# Microcontroller.net
KiCad netlist of a schematic drawn in Altium Designer
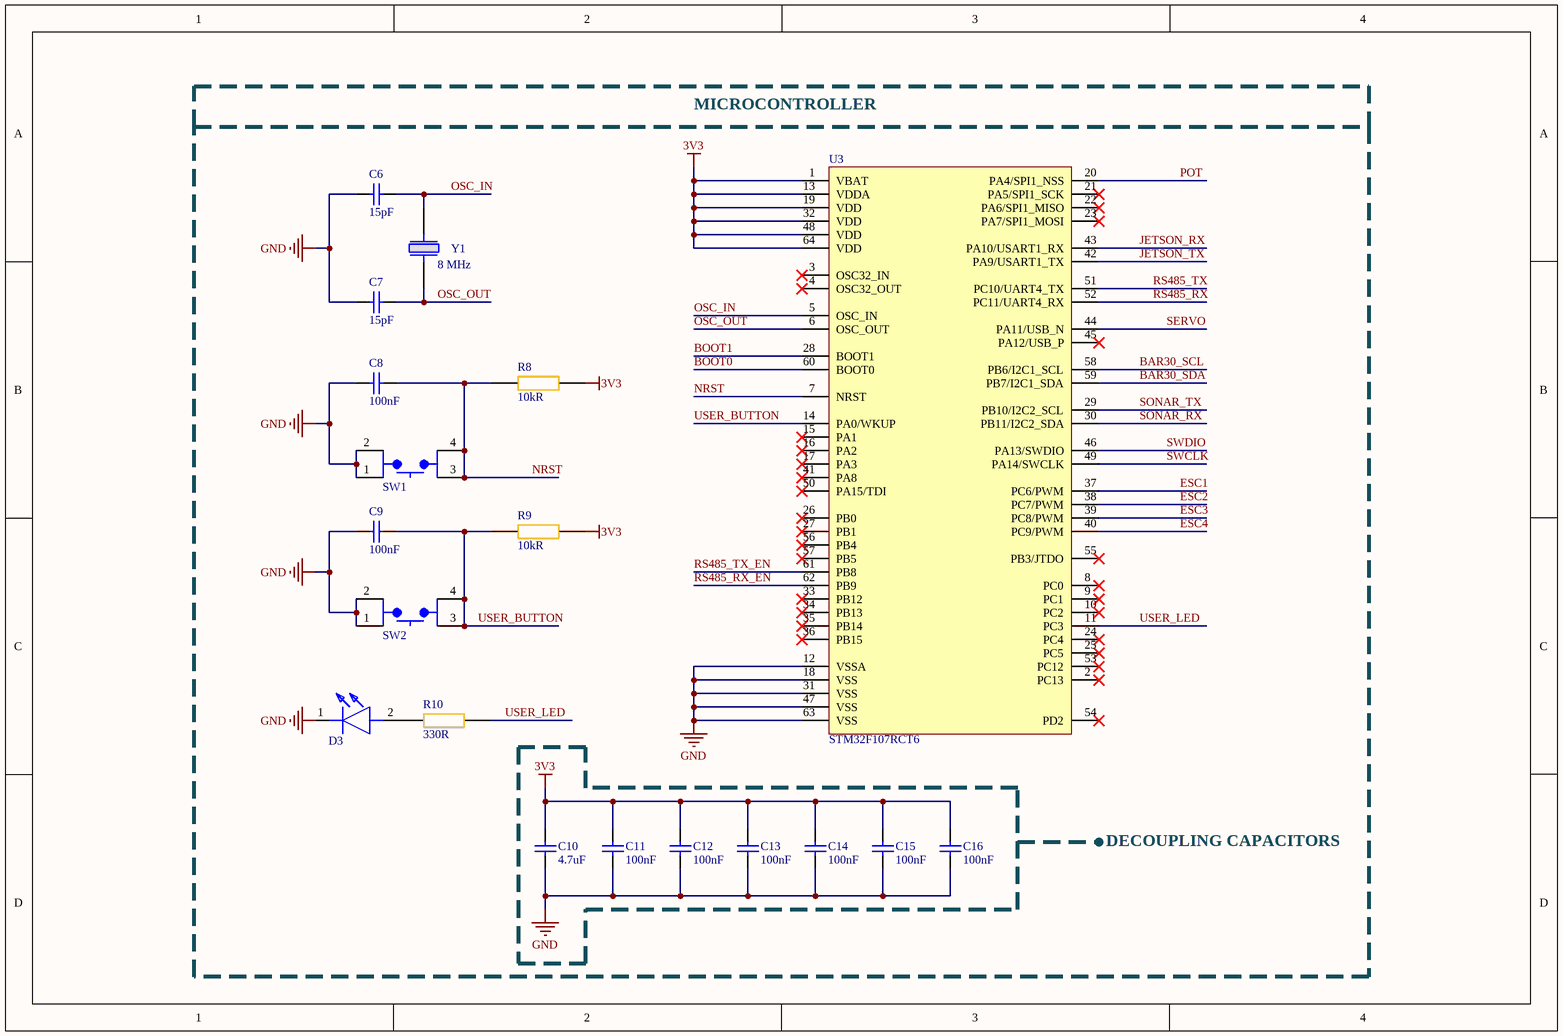
[diagram p0: Microcontroller.SchDoc]

(export (version "E")
  (design (tool "Eeschema 10.0.6"))
  (components
    (comp (ref "C6")
      (value "15pF")
      (footprint "WCAP-CSGP_0603_L1.6W0.8H0.8_Reflow")
      (description "WCAP-CSGP Multilayer Ceramic Chip Capacitor, General Purpose, size 0603, NP0, 15pF, 16VDC")
      (fields
        (field (name "MANUFACTURER PART NUMBER") "885012006018")
        (field (name "MANUFACTURER") "Wurth Elektronik")
      )
      (libsource (lib "WE - Passive Components") (part "Capacitor_Non-Polarized"))
    )
    (comp (ref "C7")
      (value "15pF")
      (footprint "WCAP-CSGP_0603_L1.6W0.8H0.8_Reflow")
      (description "WCAP-CSGP Multilayer Ceramic Chip Capacitor, General Purpose, size 0603, NP0, 15pF, 16VDC")
      (fields
        (field (name "MANUFACTURER PART NUMBER") "885012006018")
        (field (name "MANUFACTURER") "Wurth Elektronik")
      )
      (libsource (lib "WE - Passive Components") (part "Capacitor_Non-Polarized"))
    )
    (comp (ref "C8")
      (value "100nF")
      (footprint "WCAP-CSGP_0603_L1.6W0.8H0.8_Reflow")
      (description "WCAP-CSGP Multilayer Ceramic Chip Capacitor, General Purpose, size 0603, X7R, 100nF, 10VDC")
      (fields
        (field (name "MANUFACTURER PART NUMBER") "885012206020")
        (field (name "MANUFACTURER") "Wurth Elektronik")
      )
      (libsource (lib "WE - Passive Components") (part "Capacitor_Non-Polarized"))
    )
    (comp (ref "C9")
      (value "100nF")
      (footprint "WCAP-CSGP_0603_L1.6W0.8H0.8_Reflow")
      (description "WCAP-CSGP Multilayer Ceramic Chip Capacitor, General Purpose, size 0603, X7R, 100nF, 10VDC")
      (fields
        (field (name "MANUFACTURER PART NUMBER") "885012206020")
        (field (name "MANUFACTURER") "Wurth Elektronik")
      )
      (libsource (lib "WE - Passive Components") (part "Capacitor_Non-Polarized"))
    )
    (comp (ref "C10")
      (value "4.7uF")
      (footprint "WCAP-CSGP_0805_L2W1.25H1.25")
      (description "WCAP-CSGP Multilayer Ceramic Chip Capacitor, General Purpose, size 0805, X7R, 4.7µF, 16VDC")
      (fields
        (field (name "MANUFACTURER PART NUMBER") "885012207053")
        (field (name "MANUFACTURER") "Wurth Elektronik")
      )
      (libsource (lib "WE - Passive Components") (part "Capacitor_Non-Polarized"))
    )
    (comp (ref "C11")
      (value "100nF")
      (footprint "WCAP-CSGP_0603_L1.6W0.8H0.8_Reflow")
      (description "WCAP-CSGP Multilayer Ceramic Chip Capacitor, General Purpose, size 0603, X7R, 100nF, 16VDC")
      (fields
        (field (name "MANUFACTURER PART NUMBER") "885012206046")
        (field (name "MANUFACTURER") "Wurth Elektronik")
      )
      (libsource (lib "WE - Passive Components") (part "Capacitor_Non-Polarized"))
    )
    (comp (ref "C12")
      (value "100nF")
      (footprint "WCAP-CSGP_0603_L1.6W0.8H0.8_Reflow")
      (description "WCAP-CSGP Multilayer Ceramic Chip Capacitor, General Purpose, size 0603, X7R, 100nF, 16VDC")
      (fields
        (field (name "MANUFACTURER PART NUMBER") "885012206046")
        (field (name "MANUFACTURER") "Wurth Elektronik")
      )
      (libsource (lib "WE - Passive Components") (part "Capacitor_Non-Polarized"))
    )
    (comp (ref "C13")
      (value "100nF")
      (footprint "WCAP-CSGP_0603_L1.6W0.8H0.8_Reflow")
      (description "WCAP-CSGP Multilayer Ceramic Chip Capacitor, General Purpose, size 0603, X7R, 100nF, 16VDC")
      (fields
        (field (name "MANUFACTURER PART NUMBER") "885012206046")
        (field (name "MANUFACTURER") "Wurth Elektronik")
      )
      (libsource (lib "WE - Passive Components") (part "Capacitor_Non-Polarized"))
    )
    (comp (ref "C14")
      (value "100nF")
      (footprint "WCAP-CSGP_0603_L1.6W0.8H0.8_Reflow")
      (description "WCAP-CSGP Multilayer Ceramic Chip Capacitor, General Purpose, size 0603, X7R, 100nF, 16VDC")
      (fields
        (field (name "MANUFACTURER PART NUMBER") "885012206046")
        (field (name "MANUFACTURER") "Wurth Elektronik")
      )
      (libsource (lib "WE - Passive Components") (part "Capacitor_Non-Polarized"))
    )
    (comp (ref "C15")
      (value "100nF")
      (footprint "WCAP-CSGP_0603_L1.6W0.8H0.8_Reflow")
      (description "WCAP-CSGP Multilayer Ceramic Chip Capacitor, General Purpose, size 0603, X7R, 100nF, 16VDC")
      (fields
        (field (name "MANUFACTURER PART NUMBER") "885012206046")
        (field (name "MANUFACTURER") "Wurth Elektronik")
      )
      (libsource (lib "WE - Passive Components") (part "Capacitor_Non-Polarized"))
    )
    (comp (ref "C16")
      (value "100nF")
      (footprint "WCAP-CSGP_0603_L1.6W0.8H0.8_Reflow")
      (description "WCAP-CSGP Multilayer Ceramic Chip Capacitor, General Purpose, size 0603, X7R, 100nF, 16VDC")
      (fields
        (field (name "MANUFACTURER PART NUMBER") "885012206046")
        (field (name "MANUFACTURER") "Wurth Elektronik")
      )
      (libsource (lib "WE - Passive Components") (part "Capacitor_Non-Polarized"))
    )
    (comp (ref "D3")
      (value "APT1608SGC")
      (footprint "LED GREEN")
      (description "LED GREEN CLEAR 0603 SMD")
      (fields (field (name "MANUFACTURER") "Kingbright") (field (name "DESIGNED BY") "ADAK"))
      (libsource (lib "Integrated_Library5") (part "APT1608SGC"))
    )
    (comp (ref "R8")
      (value "RC0603FR-0710KP")
      (footprint "RES 0603")
      (description "RES 10K OHM 1% 1/10W 0603 SMD")
      (fields
        (field (name "MANUFACTURER") "Yageo")
        (field (name "TOLERANCE") "1%")
        (field (name "RESISTANCE") "10kR")
        (field (name "DESIGNED BY") "ADAK")
      )
      (libsource (lib "ADAK_Resistors") (part "RES 10K OHM 0603"))
    )
    (comp (ref "R9")
      (value "RC0603FR-0710KP")
      (footprint "RES 0603")
      (description "RES 10K OHM 1% 1/10W 0603 SMD")
      (fields
        (field (name "MANUFACTURER") "Yageo")
        (field (name "TOLERANCE") "1%")
        (field (name "RESISTANCE") "10kR")
        (field (name "DESIGNED BY") "ADAK")
      )
      (libsource (lib "ADAK_Resistors") (part "RES 10K OHM 0603"))
    )
    (comp (ref "R10")
      (value "RC0603FR-07330RL")
      (footprint "RES 0603")
      (description "RES 330 OHM 1% 1/10W 0603 SMD")
      (fields
        (field (name "MANUFACTURER") "Yageo")
        (field (name "TOLERANCE") "1%")
        (field (name "RESISTANCE") "330R")
        (field (name "DESIGNED BY") "ADAK")
      )
      (libsource (lib "ADAK_Resistors") (part "RES 330 OHM 0603"))
    )
    (comp (ref "SW1")
      (value "TL3305AF260QG")
      (footprint "RESET BUTTON")
      (description "SWITCH TACTILE SPST-NO 50MA 12V")
      (fields (field (name "MANUFACTURER") "E-Switch") (field (name "DESIGNED BY") "ADAK"))
      (libsource (lib "Integrated_Library5") (part "TL3305AF260QG"))
    )
    (comp (ref "SW2")
      (value "TL3305AF260QG")
      (footprint "RESET BUTTON")
      (description "SWITCH TACTILE SPST-NO 50MA 12V")
      (fields (field (name "MANUFACTURER") "E-Switch") (field (name "DESIGNED BY") "ADAK"))
      (libsource (lib "Integrated_Library5") (part "TL3305AF260QG"))
    )
    (comp (ref "U3")
      (value "STM32F107RCT6")
      (footprint "STM32F107RCT6")
      (description "IC MCU 32BIT 256KB FLASH 64LQFP")
      (fields (field (name "MANUFACTURER") "STMicroelectronics") (field (name "DESIGNED BY") "ADAK"))
      (libsource (lib "Integrated_Library5") (part "STM32F107RCT6"))
    )
    (comp (ref "Y1")
      (value "ECS-80-20-5PXDU-TR")
      (footprint "OSC")
      (description "CRYSTAL 8.0000MHZ 20PF SMD")
      (fields
        (field (name "MANUFACTURER") "ECS International")
        (field (name "FREQUENCY") "8 MHz")
        (field (name "DESIGNED BY") "ADAK")
      )
      (libsource (lib "Integrated_Library5") (part "ECS-80-20-5PXDU-TR"))
    )
  )
  (nets
    (net (code "1") (name "/BAR30_SCL") (class "Default")
      (node (ref "U3") (pin "58") (pinfunction "PB6/I2C1_SCL_58") (pintype "passive"))
    )
    (net (code "2") (name "/BAR30_SDA") (class "Default")
      (node (ref "U3") (pin "59") (pinfunction "PB7/I2C1_SDA_59") (pintype "passive"))
    )
    (net (code "3") (name "/BOOT0") (class "Default")
      (node (ref "U3") (pin "60") (pinfunction "BOOT0_60") (pintype "passive"))
    )
    (net (code "4") (name "/BOOT1") (class "Default")
      (node (ref "U3") (pin "28") (pinfunction "BOOT1_28") (pintype "passive"))
    )
    (net (code "5") (name "/ESC1") (class "Default")
      (node (ref "U3") (pin "37") (pinfunction "PC6/PWM_37") (pintype "passive"))
    )
    (net (code "6") (name "/ESC2") (class "Default")
      (node (ref "U3") (pin "38") (pinfunction "PC7/PWM_38") (pintype "passive"))
    )
    (net (code "7") (name "/ESC3") (class "Default")
      (node (ref "U3") (pin "39") (pinfunction "PC8/PWM_39") (pintype "passive"))
    )
    (net (code "8") (name "/ESC4") (class "Default")
      (node (ref "U3") (pin "40") (pinfunction "PC9/PWM_40") (pintype "passive"))
    )
    (net (code "9") (name "/JETSON_RX") (class "Default")
      (node (ref "U3") (pin "43") (pinfunction "PA10/USART1_RX_43") (pintype "passive"))
    )
    (net (code "10") (name "/JETSON_TX") (class "Default")
      (node (ref "U3") (pin "42") (pinfunction "PA9/USART1_TX_42") (pintype "passive"))
    )
    (net (code "11") (name "/NRST") (class "Default")
      (node (ref "C8") (pin "1") (pinfunction "1_1") (pintype "passive"))
      (node (ref "R8") (pin "2") (pinfunction "2_2") (pintype "passive"))
      (node (ref "SW1") (pin "3") (pinfunction "3_3") (pintype "passive"))
      (node (ref "SW1") (pin "4") (pinfunction "4_4") (pintype "passive"))
      (node (ref "U3") (pin "7") (pinfunction "NRST_7") (pintype "passive"))
    )
    (net (code "12") (name "/OSC_IN") (class "Default")
      (node (ref "C6") (pin "2") (pinfunction "2_2") (pintype "passive"))
      (node (ref "U3") (pin "5") (pinfunction "OSC_IN_5") (pintype "passive"))
      (node (ref "Y1") (pin "1") (pinfunction "1_1") (pintype "passive"))
    )
    (net (code "13") (name "/OSC_OUT") (class "Default")
      (node (ref "C7") (pin "2") (pinfunction "2_2") (pintype "passive"))
      (node (ref "U3") (pin "6") (pinfunction "OSC_OUT_6") (pintype "passive"))
      (node (ref "Y1") (pin "2") (pinfunction "2_2") (pintype "passive"))
    )
    (net (code "14") (name "/POT") (class "Default")
      (node (ref "U3") (pin "20") (pinfunction "PA4/SPI1_NSS_20") (pintype "passive"))
    )
    (net (code "15") (name "/RS485_RX") (class "Default")
      (node (ref "U3") (pin "52") (pinfunction "PC11/UART4_RX_52") (pintype "passive"))
    )
    (net (code "16") (name "/RS485_RX_EN") (class "Default")
      (node (ref "U3") (pin "62") (pinfunction "PB9_62") (pintype "passive"))
    )
    (net (code "17") (name "/RS485_TX") (class "Default")
      (node (ref "U3") (pin "51") (pinfunction "PC10/UART4_TX_51") (pintype "passive"))
    )
    (net (code "18") (name "/RS485_TX_EN") (class "Default")
      (node (ref "U3") (pin "61") (pinfunction "PB8_61") (pintype "passive"))
    )
    (net (code "19") (name "/SERVO") (class "Default")
      (node (ref "U3") (pin "44") (pinfunction "PA11/USB_N_44") (pintype "passive"))
    )
    (net (code "20") (name "/SONAR_RX") (class "Default")
      (node (ref "U3") (pin "30") (pinfunction "PB11/I2C2_SDA_30") (pintype "passive"))
    )
    (net (code "21") (name "/SONAR_TX") (class "Default")
      (node (ref "U3") (pin "29") (pinfunction "PB10/I2C2_SCL_29") (pintype "passive"))
    )
    (net (code "22") (name "/SWCLK") (class "Default")
      (node (ref "U3") (pin "49") (pinfunction "PA14/SWCLK_49") (pintype "passive"))
    )
    (net (code "23") (name "/SWDIO") (class "Default")
      (node (ref "U3") (pin "46") (pinfunction "PA13/SWDIO_46") (pintype "passive"))
    )
    (net (code "24") (name "/USER_BUTTON") (class "Default")
      (node (ref "C9") (pin "1") (pinfunction "1_1") (pintype "passive"))
      (node (ref "R9") (pin "2") (pinfunction "2_2") (pintype "passive"))
      (node (ref "SW2") (pin "3") (pinfunction "3_3") (pintype "passive"))
      (node (ref "SW2") (pin "4") (pinfunction "4_4") (pintype "passive"))
      (node (ref "U3") (pin "14") (pinfunction "PA0/WKUP_14") (pintype "passive"))
    )
    (net (code "25") (name "/USER_LED") (class "Default")
      (node (ref "R10") (pin "2") (pinfunction "2_2") (pintype "passive"))
      (node (ref "U3") (pin "11") (pinfunction "PC3_11") (pintype "passive"))
    )
    (net (code "26") (name "3V3") (class "Default")
      (node (ref "C10") (pin "2") (pinfunction "2_2") (pintype "passive"))
      (node (ref "C11") (pin "2") (pinfunction "2_2") (pintype "passive"))
      (node (ref "C12") (pin "2") (pinfunction "2_2") (pintype "passive"))
      (node (ref "C13") (pin "2") (pinfunction "2_2") (pintype "passive"))
      (node (ref "C14") (pin "2") (pinfunction "2_2") (pintype "passive"))
      (node (ref "C15") (pin "2") (pinfunction "2_2") (pintype "passive"))
      (node (ref "C16") (pin "2") (pinfunction "2_2") (pintype "passive"))
      (node (ref "R8") (pin "1") (pinfunction "1_1") (pintype "passive"))
      (node (ref "R9") (pin "1") (pinfunction "1_1") (pintype "passive"))
      (node (ref "U3") (pin "1") (pinfunction "VBAT_1") (pintype "passive"))
      (node (ref "U3") (pin "13") (pinfunction "VDDA_13") (pintype "passive"))
      (node (ref "U3") (pin "19") (pinfunction "VDD_19") (pintype "passive"))
      (node (ref "U3") (pin "32") (pinfunction "VDD_32") (pintype "passive"))
      (node (ref "U3") (pin "48") (pinfunction "VDD_48") (pintype "passive"))
      (node (ref "U3") (pin "64") (pinfunction "VDD_64") (pintype "passive"))
    )
    (net (code "27") (name "GND") (class "Default")
      (node (ref "C10") (pin "1") (pinfunction "1_1") (pintype "passive"))
      (node (ref "C11") (pin "1") (pinfunction "1_1") (pintype "passive"))
      (node (ref "C12") (pin "1") (pinfunction "1_1") (pintype "passive"))
      (node (ref "C13") (pin "1") (pinfunction "1_1") (pintype "passive"))
      (node (ref "C14") (pin "1") (pinfunction "1_1") (pintype "passive"))
      (node (ref "C15") (pin "1") (pinfunction "1_1") (pintype "passive"))
      (node (ref "C16") (pin "1") (pinfunction "1_1") (pintype "passive"))
      (node (ref "C6") (pin "1") (pinfunction "1_1") (pintype "passive"))
      (node (ref "C7") (pin "1") (pinfunction "1_1") (pintype "passive"))
      (node (ref "C8") (pin "2") (pinfunction "2_2") (pintype "passive"))
      (node (ref "C9") (pin "2") (pinfunction "2_2") (pintype "passive"))
      (node (ref "D3") (pin "1") (pinfunction "K_1") (pintype "passive"))
      (node (ref "SW1") (pin "1") (pinfunction "1_1") (pintype "passive"))
      (node (ref "SW1") (pin "2") (pinfunction "2_2") (pintype "passive"))
      (node (ref "SW2") (pin "1") (pinfunction "1_1") (pintype "passive"))
      (node (ref "SW2") (pin "2") (pinfunction "2_2") (pintype "passive"))
      (node (ref "U3") (pin "12") (pinfunction "VSSA_12") (pintype "passive"))
      (node (ref "U3") (pin "18") (pinfunction "VSS_18") (pintype "passive"))
      (node (ref "U3") (pin "31") (pinfunction "VSS_31") (pintype "passive"))
      (node (ref "U3") (pin "47") (pinfunction "VSS_47") (pintype "passive"))
      (node (ref "U3") (pin "63") (pinfunction "VSS_63") (pintype "passive"))
    )
    (net (code "28") (name "Net-(D3-A)") (class "Default")
      (node (ref "D3") (pin "2") (pinfunction "A_2") (pintype "passive"))
      (node (ref "R10") (pin "1") (pinfunction "1_1") (pintype "passive"))
    )
    (net (code "29") (name "unconnected-(U3-OSC32_IN-Pad3)") (class "Default")
      (node (ref "U3") (pin "3") (pinfunction "OSC32_IN_3") (pintype "passive+no_connect"))
    )
    (net (code "30") (name "unconnected-(U3-OSC32_OUT-Pad4)") (class "Default")
      (node (ref "U3") (pin "4") (pinfunction "OSC32_OUT_4") (pintype "passive+no_connect"))
    )
    (net (code "31") (name "unconnected-(U3-PA1-Pad15)") (class "Default")
      (node (ref "U3") (pin "15") (pinfunction "PA1_15") (pintype "passive+no_connect"))
    )
    (net (code "32") (name "unconnected-(U3-PA2-Pad16)") (class "Default")
      (node (ref "U3") (pin "16") (pinfunction "PA2_16") (pintype "passive+no_connect"))
    )
    (net (code "33") (name "unconnected-(U3-PA3-Pad17)") (class "Default")
      (node (ref "U3") (pin "17") (pinfunction "PA3_17") (pintype "passive+no_connect"))
    )
    (net (code "34") (name "unconnected-(U3-PA5{slash}SPI1_SCK-Pad21)") (class "Default")
      (node (ref "U3") (pin "21") (pinfunction "PA5/SPI1_SCK_21") (pintype "passive+no_connect"))
    )
    (net (code "35") (name "unconnected-(U3-PA6{slash}SPI1_MISO-Pad22)") (class "Default")
      (node (ref "U3") (pin "22") (pinfunction "PA6/SPI1_MISO_22") (pintype "passive+no_connect"))
    )
    (net (code "36") (name "unconnected-(U3-PA7{slash}SPI1_MOSI-Pad23)") (class "Default")
      (node (ref "U3") (pin "23") (pinfunction "PA7/SPI1_MOSI_23") (pintype "passive+no_connect"))
    )
    (net (code "37") (name "unconnected-(U3-PA8-Pad41)") (class "Default")
      (node (ref "U3") (pin "41") (pinfunction "PA8_41") (pintype "passive+no_connect"))
    )
    (net (code "38") (name "unconnected-(U3-PA12{slash}USB_P-Pad45)") (class "Default")
      (node (ref "U3") (pin "45") (pinfunction "PA12/USB_P_45") (pintype "passive+no_connect"))
    )
    (net (code "39") (name "unconnected-(U3-PA15{slash}TDI-Pad50)") (class "Default")
      (node (ref "U3") (pin "50") (pinfunction "PA15/TDI_50") (pintype "passive+no_connect"))
    )
    (net (code "40") (name "unconnected-(U3-PB0-Pad26)") (class "Default")
      (node (ref "U3") (pin "26") (pinfunction "PB0_26") (pintype "passive+no_connect"))
    )
    (net (code "41") (name "unconnected-(U3-PB1-Pad27)") (class "Default")
      (node (ref "U3") (pin "27") (pinfunction "PB1_27") (pintype "passive+no_connect"))
    )
    (net (code "42") (name "unconnected-(U3-PB3{slash}JTDO-Pad55)") (class "Default")
      (node (ref "U3") (pin "55") (pinfunction "PB3/JTDO_55") (pintype "passive+no_connect"))
    )
    (net (code "43") (name "unconnected-(U3-PB4-Pad56)") (class "Default")
      (node (ref "U3") (pin "56") (pinfunction "PB4_56") (pintype "passive+no_connect"))
    )
    (net (code "44") (name "unconnected-(U3-PB5-Pad57)") (class "Default")
      (node (ref "U3") (pin "57") (pinfunction "PB5_57") (pintype "passive+no_connect"))
    )
    (net (code "45") (name "unconnected-(U3-PB12-Pad33)") (class "Default")
      (node (ref "U3") (pin "33") (pinfunction "PB12_33") (pintype "passive+no_connect"))
    )
    (net (code "46") (name "unconnected-(U3-PB13-Pad34)") (class "Default")
      (node (ref "U3") (pin "34") (pinfunction "PB13_34") (pintype "passive+no_connect"))
    )
    (net (code "47") (name "unconnected-(U3-PB14-Pad35)") (class "Default")
      (node (ref "U3") (pin "35") (pinfunction "PB14_35") (pintype "passive+no_connect"))
    )
    (net (code "48") (name "unconnected-(U3-PB15-Pad36)") (class "Default")
      (node (ref "U3") (pin "36") (pinfunction "PB15_36") (pintype "passive+no_connect"))
    )
    (net (code "49") (name "unconnected-(U3-PC0-Pad8)") (class "Default")
      (node (ref "U3") (pin "8") (pinfunction "PC0_8") (pintype "passive+no_connect"))
    )
    (net (code "50") (name "unconnected-(U3-PC1-Pad9)") (class "Default")
      (node (ref "U3") (pin "9") (pinfunction "PC1_9") (pintype "passive+no_connect"))
    )
    (net (code "51") (name "unconnected-(U3-PC2-Pad10)") (class "Default")
      (node (ref "U3") (pin "10") (pinfunction "PC2_10") (pintype "passive+no_connect"))
    )
    (net (code "52") (name "unconnected-(U3-PC4-Pad24)") (class "Default")
      (node (ref "U3") (pin "24") (pinfunction "PC4_24") (pintype "passive+no_connect"))
    )
    (net (code "53") (name "unconnected-(U3-PC5-Pad25)") (class "Default")
      (node (ref "U3") (pin "25") (pinfunction "PC5_25") (pintype "passive+no_connect"))
    )
    (net (code "54") (name "unconnected-(U3-PC12-Pad53)") (class "Default")
      (node (ref "U3") (pin "53") (pinfunction "PC12_53") (pintype "passive+no_connect"))
    )
    (net (code "55") (name "unconnected-(U3-PC13-Pad2)") (class "Default")
      (node (ref "U3") (pin "2") (pinfunction "PC13_2") (pintype "passive+no_connect"))
    )
    (net (code "56") (name "unconnected-(U3-PD2-Pad54)") (class "Default")
      (node (ref "U3") (pin "54") (pinfunction "PD2_54") (pintype "passive+no_connect"))
    )
  )
)
